# USB_Interface.net
KiCad netlist of a schematic drawn in Altium Designer
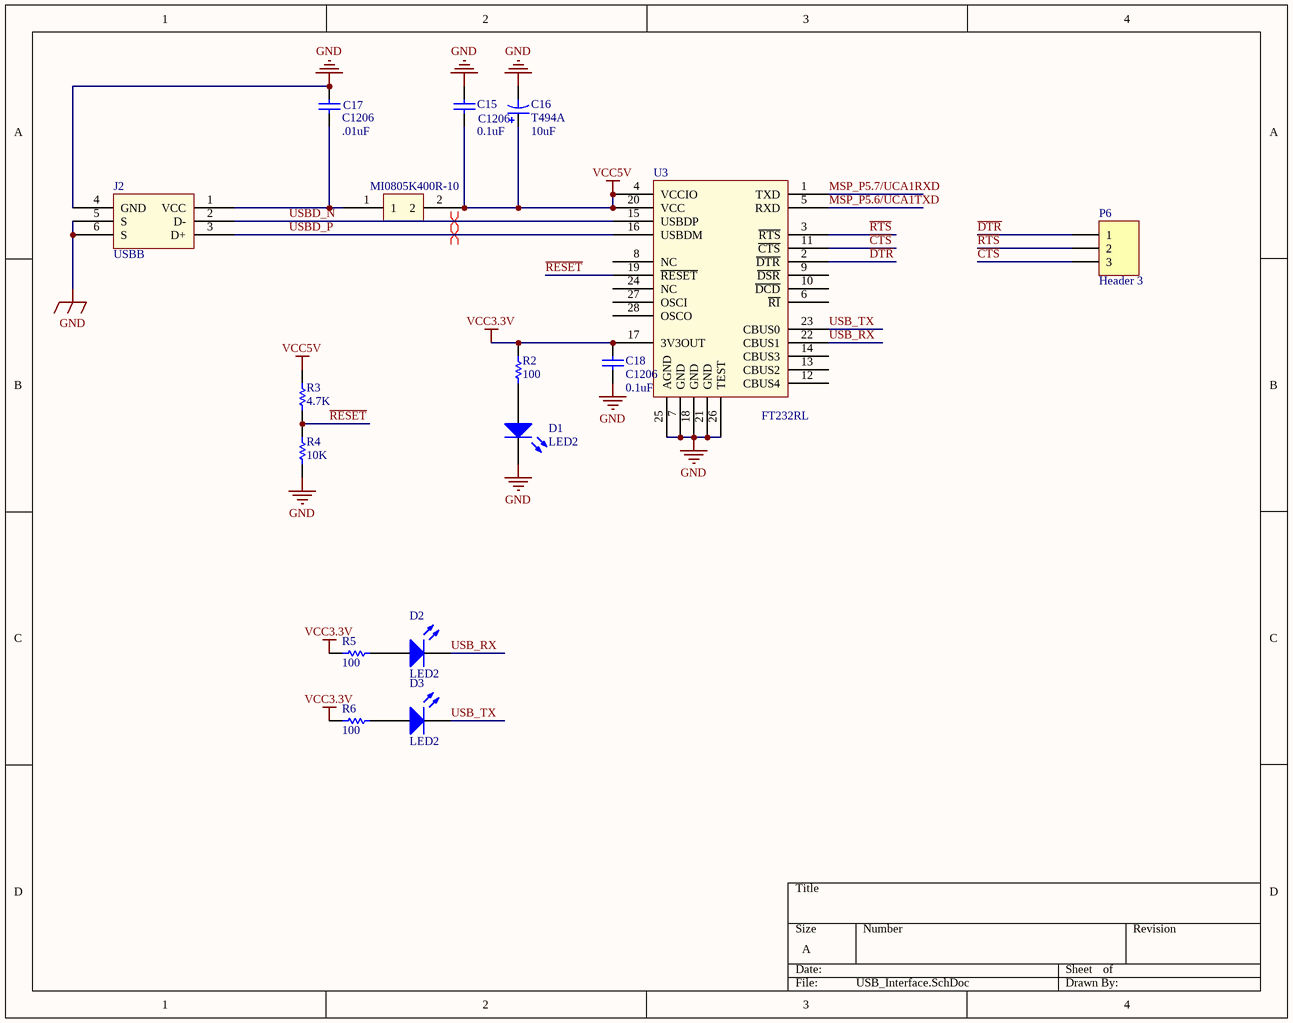
[diagram p0: USB_Interface.SchDoc]

(export (version "E")
  (design (tool "Eeschema 10.0.6"))
  (components
    (comp (ref "C15")
      (value "C1206")
      (footprint "1206")
      (description "Ceramic Chip Capacitor - Standard")
      (fields (field (name "ALTIUM_VALUE") "0.1uF") (field (name "PUBLISHER") "Altium Limited"))
      (libsource (lib "KEMET Chip Capacitor") (part "C1206"))
    )
    (comp (ref "C16")
      (value "T494A")
      (footprint "A")
      (description "Solid Tantalum Chip Capacitor, Standard T494 Series - Low ESR, Industrial Grade")
      (fields (field (name "ALTIUM_VALUE") "10uF") (field (name "PUBLISHER") "Altium Limited"))
      (libsource (lib "KEMET Chip Capacitor") (part "T494A"))
    )
    (comp (ref "C17")
      (value "C1206")
      (footprint "1206")
      (description "Ceramic Chip Capacitor - Standard")
      (fields (field (name "ALTIUM_VALUE") ".01uF") (field (name "PUBLISHER") "Altium Limited"))
      (libsource (lib "KEMET Chip Capacitor") (part "C1206"))
    )
    (comp (ref "C18")
      (value "C1206")
      (footprint "1206")
      (description "Ceramic Chip Capacitor - Standard")
      (fields (field (name "ALTIUM_VALUE") "0.1uF") (field (name "PUBLISHER") "Altium Limited"))
      (libsource (lib "KEMET Chip Capacitor") (part "C1206"))
    )
    (comp (ref "D1")
      (value "LED2")
      (footprint "LED_LiteOn:LED_LiteOn_footprint")
      (description "Typical RED, GREEN, YELLOW, AMBER GaAs LED")
      (libsource (lib "Miscellaneous Devices") (part "LED2"))
    )
    (comp (ref "D2")
      (value "LED2")
      (footprint "LED_LiteOn:LED_LiteOn_footprint")
      (description "Typical RED, GREEN, YELLOW, AMBER GaAs LED")
      (libsource (lib "Miscellaneous Devices") (part "LED2"))
    )
    (comp (ref "D3")
      (value "LED2")
      (footprint "LED_LiteOn:LED_LiteOn_footprint")
      (description "Typical RED, GREEN, YELLOW, AMBER GaAs LED")
      (libsource (lib "Miscellaneous Devices") (part "LED2"))
    )
    (comp (ref "J2")
      (value "USBB")
      (footprint "usbb_pcb:PCBComponent_1")
      (libsource (lib "usbb_lib") (part "USBB"))
    )
    (comp (ref "P6")
      (value "Header 3")
      (footprint "HDR1X3")
      (description "Header, 3-Pin")
      (fields (field (name "PUBLISHER") "Altium Limited"))
      (libsource (lib "Miscellaneous Connectors") (part "Header 3"))
    )
    (comp (ref "R2")
      (value "100")
      (footprint "8-1206")
      (description "Thick Film Chip Resistor, 1 Ohm to 10M Ohm Range, 5% Tolerance, 1206 Size, 0.25 W")
      (fields (field (name "PUBLISHER") "Altium Limited"))
      (libsource (lib "Panasonic Resistor") (part "ERJ8GE"))
    )
    (comp (ref "R3")
      (value "4.7K")
      (footprint "8-1206")
      (description "Thick Film Chip Resistor, 1 Ohm to 10M Ohm Range, 5% Tolerance, 1206 Size, 0.25 W")
      (fields (field (name "PUBLISHER") "Altium Limited"))
      (libsource (lib "Panasonic Resistor") (part "ERJ8GE"))
    )
    (comp (ref "R4")
      (value "10K")
      (footprint "8-1206")
      (description "Thick Film Chip Resistor, 1 Ohm to 10M Ohm Range, 5% Tolerance, 1206 Size, 0.25 W")
      (fields (field (name "PUBLISHER") "Altium Limited"))
      (libsource (lib "Panasonic Resistor") (part "ERJ8GE"))
    )
    (comp (ref "R5")
      (value "100")
      (footprint "8-1206")
      (description "Thick Film Chip Resistor, 1 Ohm to 10M Ohm Range, 5% Tolerance, 1206 Size, 0.25 W")
      (fields (field (name "PUBLISHER") "Altium Limited"))
      (libsource (lib "Panasonic Resistor") (part "ERJ8GE"))
    )
    (comp (ref "R6")
      (value "100")
      (footprint "8-1206")
      (description "Thick Film Chip Resistor, 1 Ohm to 10M Ohm Range, 5% Tolerance, 1206 Size, 0.25 W")
      (fields (field (name "PUBLISHER") "Altium Limited"))
      (libsource (lib "Panasonic Resistor") (part "ERJ8GE"))
    )
    (comp (ref "U3")
      (value "FT232RL")
      (footprint "SOP65P780X200-28N")
      (libsource (lib "FT232RL") (part "FT232RL"))
    )
    (comp (ref "U4")
      (value "MI0805K400R-10")
      (footprint "INDC2012X11N")
      (description "ferrite bead")
      (libsource (lib "ferrite_bead") (part "ferrite bead"))
    )
  )
  (nets
    (net (code "1") (name "/MSP_P5.6{slash}UCA1TXD") (class "Default")
      (node (ref "U3") (pin "5") (pinfunction "RXD_5") (pintype "passive"))
    )
    (net (code "2") (name "/MSP_P5.7{slash}UCA1RXD") (class "Default")
      (node (ref "U3") (pin "1") (pinfunction "TXD_1") (pintype "passive"))
    )
    (net (code "3") (name "/USBD_N") (class "Default")
      (node (ref "J2") (pin "2") (pinfunction "D-_2") (pintype "passive"))
      (node (ref "U3") (pin "15") (pinfunction "USBDP_15") (pintype "passive"))
    )
    (net (code "4") (name "/USBD_P") (class "Default")
      (node (ref "J2") (pin "3") (pinfunction "D+_3") (pintype "passive"))
      (node (ref "U3") (pin "16") (pinfunction "USBDM_16") (pintype "passive"))
    )
    (net (code "5") (name "/USB_RX") (class "Default")
      (node (ref "D2") (pin "2") (pinfunction "K_2") (pintype "passive"))
      (node (ref "U3") (pin "22") (pinfunction "CBUS1_22") (pintype "passive"))
    )
    (net (code "6") (name "/USB_TX") (class "Default")
      (node (ref "D3") (pin "2") (pinfunction "K_2") (pintype "passive"))
      (node (ref "U3") (pin "23") (pinfunction "CBUS0_23") (pintype "passive"))
    )
    (net (code "7") (name "/~{CTS}") (class "Default")
      (node (ref "P6") (pin "3") (pinfunction "3_3") (pintype "passive"))
      (node (ref "U3") (pin "11") (pinfunction "~{CTS}_11") (pintype "passive"))
    )
    (net (code "8") (name "/~{DTR}") (class "Default")
      (node (ref "P6") (pin "1") (pinfunction "1_1") (pintype "passive"))
      (node (ref "U3") (pin "2") (pinfunction "~{DTR}_2") (pintype "passive"))
    )
    (net (code "9") (name "/~{RESET}") (class "Default")
      (node (ref "R3") (pin "2") (pinfunction "2_2") (pintype "passive"))
      (node (ref "R4") (pin "1") (pinfunction "1_1") (pintype "passive"))
      (node (ref "U3") (pin "19") (pinfunction "~{RESET}_19") (pintype "passive"))
    )
    (net (code "10") (name "/~{RTS}") (class "Default")
      (node (ref "P6") (pin "2") (pinfunction "2_2") (pintype "passive"))
      (node (ref "U3") (pin "3") (pinfunction "~{RTS}_3") (pintype "passive"))
    )
    (net (code "11") (name "GND") (class "Default")
      (node (ref "C15") (pin "2") (pinfunction "2_2") (pintype "passive"))
      (node (ref "C16") (pin "2") (pinfunction "2_2") (pintype "passive"))
      (node (ref "C17") (pin "1") (pinfunction "1_1") (pintype "passive"))
      (node (ref "C18") (pin "1") (pinfunction "1_1") (pintype "passive"))
      (node (ref "D1") (pin "2") (pinfunction "K_2") (pintype "passive"))
      (node (ref "J2") (pin "4") (pinfunction "GND_4") (pintype "power_in"))
      (node (ref "J2") (pin "5") (pinfunction "S_5") (pintype "passive"))
      (node (ref "J2") (pin "6") (pinfunction "S_6") (pintype "passive"))
      (node (ref "R4") (pin "2") (pinfunction "2_2") (pintype "passive"))
      (node (ref "U3") (pin "18") (pinfunction "GND_18") (pintype "power_in"))
      (node (ref "U3") (pin "21") (pinfunction "GND_21") (pintype "power_in"))
      (node (ref "U3") (pin "25") (pinfunction "AGND_25") (pintype "power_in"))
      (node (ref "U3") (pin "26") (pinfunction "TEST_26") (pintype "passive"))
      (node (ref "U3") (pin "7") (pinfunction "GND_7") (pintype "power_in"))
    )
    (net (code "12") (name "Net-(D1-A)") (class "Default")
      (node (ref "D1") (pin "1") (pinfunction "A_1") (pintype "passive"))
      (node (ref "R2") (pin "1") (pinfunction "1_1") (pintype "passive"))
    )
    (net (code "13") (name "Net-(D2-A)") (class "Default")
      (node (ref "D2") (pin "1") (pinfunction "A_1") (pintype "passive"))
      (node (ref "R5") (pin "2") (pinfunction "2_2") (pintype "passive"))
    )
    (net (code "14") (name "Net-(D3-A)") (class "Default")
      (node (ref "D3") (pin "1") (pinfunction "A_1") (pintype "passive"))
      (node (ref "R6") (pin "2") (pinfunction "2_2") (pintype "passive"))
    )
    (net (code "15") (name "Net-(J2-VCC)") (class "Default")
      (node (ref "C17") (pin "2") (pinfunction "2_2") (pintype "passive"))
      (node (ref "J2") (pin "1") (pinfunction "VCC_1") (pintype "power_in"))
      (node (ref "U4") (pin "1") (pinfunction "1_1") (pintype "passive"))
    )
    (net (code "16") (name "VCC3.3V") (class "Default")
      (node (ref "C18") (pin "2") (pinfunction "2_2") (pintype "passive"))
      (node (ref "R2") (pin "2") (pinfunction "2_2") (pintype "passive"))
      (node (ref "R5") (pin "1") (pinfunction "1_1") (pintype "passive"))
      (node (ref "R6") (pin "1") (pinfunction "1_1") (pintype "passive"))
      (node (ref "U3") (pin "17") (pinfunction "3V3OUT_17") (pintype "power_in"))
    )
    (net (code "17") (name "VCC5V") (class "Default")
      (node (ref "C15") (pin "1") (pinfunction "1_1") (pintype "passive"))
      (node (ref "C16") (pin "1") (pinfunction "1_1") (pintype "passive"))
      (node (ref "R3") (pin "1") (pinfunction "1_1") (pintype "passive"))
      (node (ref "U3") (pin "20") (pinfunction "VCC_20") (pintype "power_in"))
      (node (ref "U3") (pin "4") (pinfunction "VCCIO_4") (pintype "power_in"))
      (node (ref "U4") (pin "2") (pinfunction "2_2") (pintype "passive"))
    )
    (net (code "18") (name "unconnected-(U3-CBUS2-Pad13)") (class "Default")
      (node (ref "U3") (pin "13") (pinfunction "CBUS2_13") (pintype "passive"))
    )
    (net (code "19") (name "unconnected-(U3-CBUS3-Pad14)") (class "Default")
      (node (ref "U3") (pin "14") (pinfunction "CBUS3_14") (pintype "passive"))
    )
    (net (code "20") (name "unconnected-(U3-CBUS4-Pad12)") (class "Default")
      (node (ref "U3") (pin "12") (pinfunction "CBUS4_12") (pintype "passive"))
    )
    (net (code "21") (name "unconnected-(U3-NC-Pad8)") (class "Default")
      (node (ref "U3") (pin "8") (pinfunction "NC_8") (pintype "passive"))
    )
    (net (code "22") (name "unconnected-(U3-NC-Pad24)") (class "Default")
      (node (ref "U3") (pin "24") (pinfunction "NC_24") (pintype "passive"))
    )
    (net (code "23") (name "unconnected-(U3-OSCI-Pad27)") (class "Default")
      (node (ref "U3") (pin "27") (pinfunction "OSCI_27") (pintype "passive"))
    )
    (net (code "24") (name "unconnected-(U3-OSCO-Pad28)") (class "Default")
      (node (ref "U3") (pin "28") (pinfunction "OSCO_28") (pintype "passive"))
    )
    (net (code "25") (name "unconnected-(U3-~{DCD}-Pad10)") (class "Default")
      (node (ref "U3") (pin "10") (pinfunction "~{DCD}_10") (pintype "passive"))
    )
    (net (code "26") (name "unconnected-(U3-~{DSR}-Pad9)") (class "Default")
      (node (ref "U3") (pin "9") (pinfunction "~{DSR}_9") (pintype "passive"))
    )
    (net (code "27") (name "unconnected-(U3-~{RI}-Pad6)") (class "Default")
      (node (ref "U3") (pin "6") (pinfunction "~{RI}_6") (pintype "passive"))
    )
  )
)
